# wearable_button.net
KiCad netlist of a schematic drawn in EAGLE
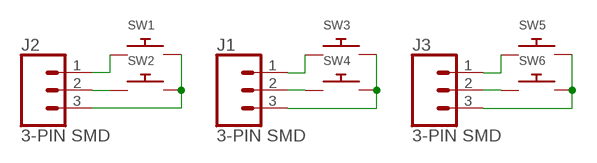
[diagram p0: schematic, sheet 1]

(export (version "E")
  (design (tool "Eeschema 10.0.6"))
  (components
    (comp (ref "J1")
      (value "3-PIN SMD")
      (footprint "eagle-import:JST-3-SMD")
      (libsource (lib "eagle-import") (part "CONN_03JST-SMD"))
    )
    (comp (ref "J2")
      (value "3-PIN SMD")
      (footprint "eagle-import:JST-3-SMD")
      (libsource (lib "eagle-import") (part "CONN_03JST-SMD"))
    )
    (comp (ref "J3")
      (value "3-PIN SMD")
      (footprint "eagle-import:JST-3-SMD")
      (libsource (lib "eagle-import") (part "CONN_03JST-SMD"))
    )
    (comp (ref "SW1")
      (value "SWITCH_PUSHBUTTONSOFTTOUCHSMD_SJ")
      (footprint "eagle-import:PUSHBUTTON_SMD_SJ")
      (libsource (lib "eagle-import") (part "SWITCH_PUSHBUTTONSOFTTOUCHSMD_SJ"))
    )
    (comp (ref "SW2")
      (value "SWITCH_PUSHBUTTONSOFTTOUCHSMD_SJ")
      (footprint "eagle-import:PUSHBUTTON_SMD_SJ")
      (libsource (lib "eagle-import") (part "SWITCH_PUSHBUTTONSOFTTOUCHSMD_SJ"))
    )
    (comp (ref "SW3")
      (value "SWITCH_PUSHBUTTONSOFTTOUCHSMD_SJ")
      (footprint "eagle-import:PUSHBUTTON_SMD_SJ")
      (libsource (lib "eagle-import") (part "SWITCH_PUSHBUTTONSOFTTOUCHSMD_SJ"))
    )
    (comp (ref "SW4")
      (value "SWITCH_PUSHBUTTONSOFTTOUCHSMD_SJ")
      (footprint "eagle-import:PUSHBUTTON_SMD_SJ")
      (libsource (lib "eagle-import") (part "SWITCH_PUSHBUTTONSOFTTOUCHSMD_SJ"))
    )
    (comp (ref "SW5")
      (value "SWITCH_PUSHBUTTONSOFTTOUCHSMD_SJ")
      (footprint "eagle-import:PUSHBUTTON_SMD_SJ")
      (libsource (lib "eagle-import") (part "SWITCH_PUSHBUTTONSOFTTOUCHSMD_SJ"))
    )
    (comp (ref "SW6")
      (value "SWITCH_PUSHBUTTONSOFTTOUCHSMD_SJ")
      (footprint "eagle-import:PUSHBUTTON_SMD_SJ")
      (libsource (lib "eagle-import") (part "SWITCH_PUSHBUTTONSOFTTOUCHSMD_SJ"))
    )
  )
  (nets
    (net (code "1") (name "Net-(J1-1)") (class "Default")
      (node (ref "J1") (pin "3") (pinfunction "1_3") (pintype "passive"))
      (node (ref "SW3") (pin "P$2") (pinfunction "P$2_P$2") (pintype "passive"))
      (node (ref "SW4") (pin "P$2") (pinfunction "P$2_P$2") (pintype "passive"))
    )
    (net (code "2") (name "Net-(J1-3)") (class "Default")
      (node (ref "J1") (pin "1") (pinfunction "3_1") (pintype "passive"))
      (node (ref "SW3") (pin "P$1") (pinfunction "P$1_P$1") (pintype "passive"))
    )
    (net (code "3") (name "Net-(J1-Pad2)") (class "Default")
      (node (ref "J1") (pin "2") (pinfunction "2_2") (pintype "passive"))
      (node (ref "SW4") (pin "P$1") (pinfunction "P$1_P$1") (pintype "passive"))
    )
    (net (code "4") (name "Net-(J2-1)") (class "Default")
      (node (ref "J2") (pin "3") (pinfunction "1_3") (pintype "passive"))
      (node (ref "SW1") (pin "P$2") (pinfunction "P$2_P$2") (pintype "passive"))
      (node (ref "SW2") (pin "P$2") (pinfunction "P$2_P$2") (pintype "passive"))
    )
    (net (code "5") (name "Net-(J2-3)") (class "Default")
      (node (ref "J2") (pin "1") (pinfunction "3_1") (pintype "passive"))
      (node (ref "SW1") (pin "P$1") (pinfunction "P$1_P$1") (pintype "passive"))
    )
    (net (code "6") (name "Net-(J2-Pad2)") (class "Default")
      (node (ref "J2") (pin "2") (pinfunction "2_2") (pintype "passive"))
      (node (ref "SW2") (pin "P$1") (pinfunction "P$1_P$1") (pintype "passive"))
    )
    (net (code "7") (name "Net-(J3-1)") (class "Default")
      (node (ref "J3") (pin "3") (pinfunction "1_3") (pintype "passive"))
      (node (ref "SW5") (pin "P$2") (pinfunction "P$2_P$2") (pintype "passive"))
      (node (ref "SW6") (pin "P$2") (pinfunction "P$2_P$2") (pintype "passive"))
    )
    (net (code "8") (name "Net-(J3-3)") (class "Default")
      (node (ref "J3") (pin "1") (pinfunction "3_1") (pintype "passive"))
      (node (ref "SW5") (pin "P$1") (pinfunction "P$1_P$1") (pintype "passive"))
    )
    (net (code "9") (name "Net-(J3-Pad2)") (class "Default")
      (node (ref "J3") (pin "2") (pinfunction "2_2") (pintype "passive"))
      (node (ref "SW6") (pin "P$1") (pinfunction "P$1_P$1") (pintype "passive"))
    )
  )
)
